# DCDC-LMR16030.net
KiCad netlist of a schematic drawn in Altium Designer
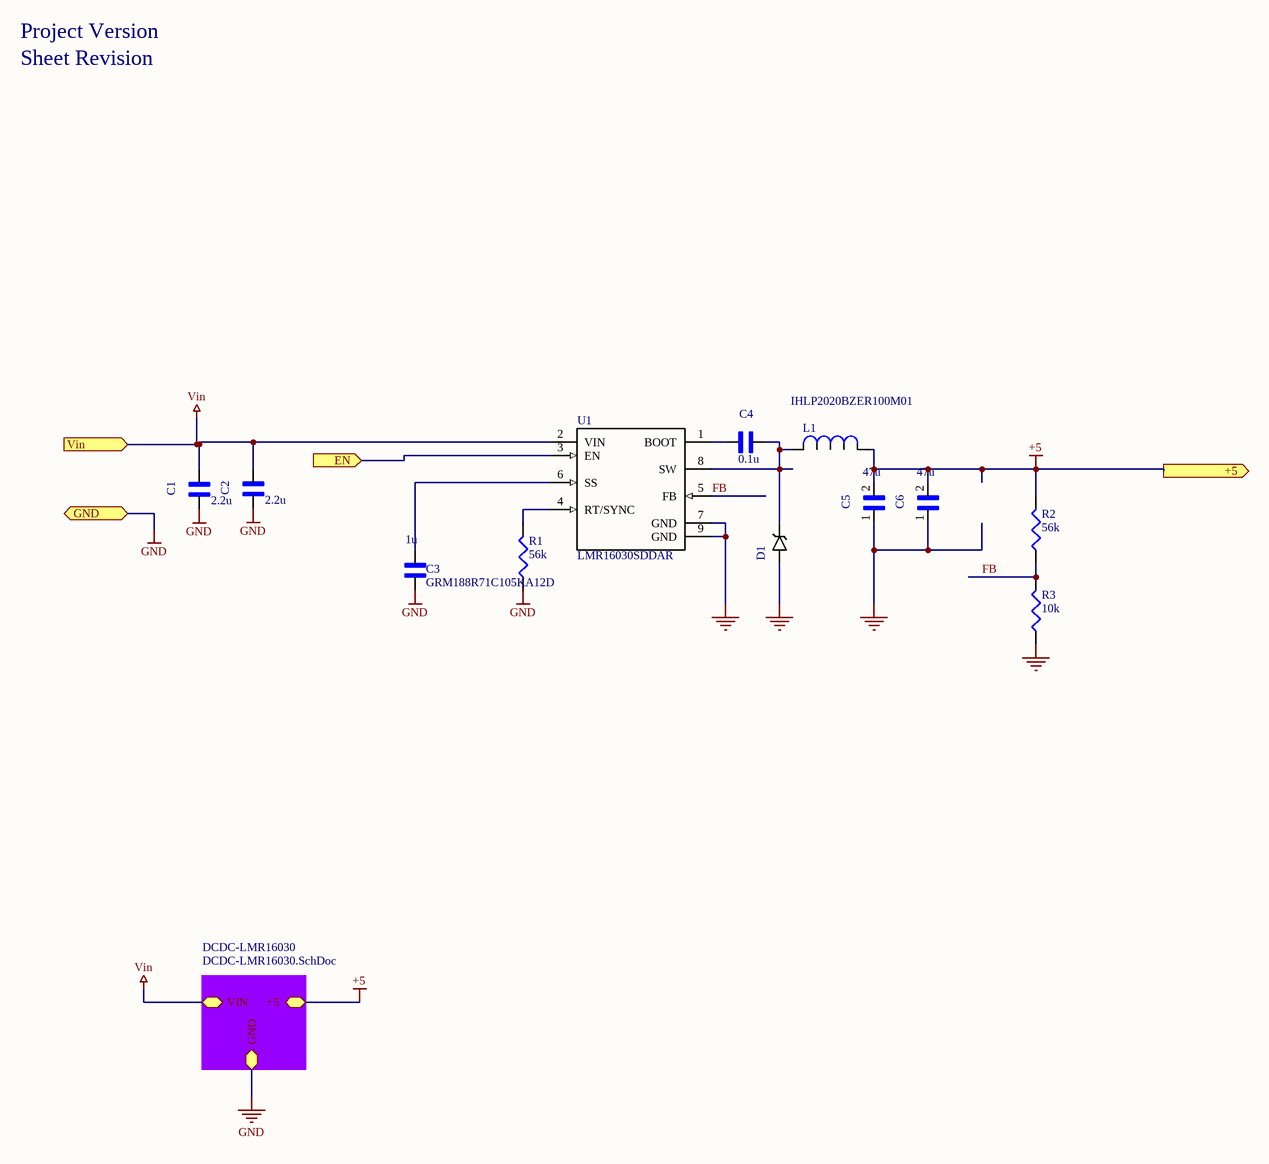
[diagram p0: DCDC-LMR16030.SchDoc]

(export (version "E")
  (design (tool "Eeschema 10.0.6"))
  (components
    (comp (ref "C1")
      (value "2.2u")
      (footprint "*CAP3216X125N")
      (description "1206 2.2 uF 50 V В±10% Tolerance X7R SMT Multilayer Ceramic Capacitor")
      (fields (field (name "MF") "Murata Electronics") (field (name "MP") "GRM31CR71H225KA88L"))
      (libsource (lib "lib") (part "GRM31CR71H225KA88L"))
    )
    (comp (ref "C2")
      (value "2.2u")
      (footprint "*CAP3216X125N")
      (description "1206 2.2 uF 50 V В±10% Tolerance X7R SMT Multilayer Ceramic Capacitor")
      (fields (field (name "MF") "Murata Electronics") (field (name "MP") "GRM31CR71H225KA88L"))
      (libsource (lib "lib") (part "GRM31CR71H225KA88L"))
    )
    (comp (ref "C3")
      (value "GRM188R71C105KA12D")
      (footprint "CAPC1608X90N")
      (description "SMD Capacitor X7R(EIA) with Capacitance: 1.0uF Tol. 10%. Rated Voltage: 16Vdc")
      (fields (field (name "MF") "Murata Electronics") (field (name "ALTIUM_VALUE") "1u"))
      (libsource (lib "lib") (part "GRM188R71C105KA12D"))
    )
    (comp (ref "C4")
      (value "0.1u")
      (footprint "*CAPC1608X90")
      (description "Cap Thin Film 0.1uf 50v 0603")
      (fields (field (name "MF") "AVX") (field (name "MP") "GX035C104MAT2-500 or CL10B104JB8NNNC"))
      (libsource (lib "lib") (part "GX035C104MAT2-500"))
    )
    (comp (ref "C5")
      (value "47u")
      (footprint "*CAPC3216X125N")
      (description "Multilayer Ceramic Capacitor, GRM Series, 47 - F, - 10%, X5R, 10 V, 1206 [3216 Metric]")
      (fields (field (name "MF") "Murata Electronics") (field (name "MP") "GRM31CR61A476KE15L"))
      (libsource (lib "lib") (part "GRM31CR61A476KE15L"))
    )
    (comp (ref "C6")
      (value "47u")
      (footprint "*CAPC3216X125N")
      (description "Multilayer Ceramic Capacitor, GRM Series, 47 - F, - 10%, X5R, 10 V, 1206 [3216 Metric]")
      (fields (field (name "MF") "Murata Electronics") (field (name "MP") "GRM31CR61A476KE15L"))
      (libsource (lib "lib") (part "GRM31CR61A476KE15L"))
    )
    (comp (ref "D1")
      (value "SK56")
      (footprint "*SMB_P6SMB62AT3G(Primary)")
      (description "Диод Шоттки 5А 60В [SMB / DO-214AA]")
      (fields (field (name "MF") "Littelfuse Inc."))
      (libsource (lib "lib") (part "SK56"))
    )
    (comp (ref "L1")
      (value "IHLP2020BZER100M01")
      (footprint "IHLP")
      (description "10ÂµH Shielded Molded Inductor 2.3A 199mOhm Max Nonstandard")
      (fields (field (name "MF") "Vishay Dale"))
      (libsource (lib "lib") (part "IHLP2020BZER100M01"))
    )
    (comp (ref "R1")
      (value "56k")
      (footprint "J1-0603")
      (description "Resistor")
      (fields (field (name "MP") "RC0603FR-0756KL") (field (name "Comment") "Res3"))
      (libsource (lib "Miscellaneous Devices") (part "Res3"))
    )
    (comp (ref "R2")
      (value "56k")
      (footprint "J1-0603")
      (description "Resistor")
      (fields (field (name "MP") "RC0603FR-0756KL") (field (name "Comment") "Res3"))
      (libsource (lib "Miscellaneous Devices") (part "Res3"))
    )
    (comp (ref "R3")
      (value "10k")
      (footprint "J1-0603")
      (description "10 kOhms 1 0.1 W 1 10 W Chip Resistor 0603 1608 Metric Thick Film")
      (fields (field (name "MF") "Yageo or NXP") (field (name "MP") "10K 1% 0603"))
      (libsource (lib "CAN_NODE_MINI") (part "RC0603FR-0710KL"))
    )
    (comp (ref "U1")
      (value "LMR16030SDDAR")
      (footprint "*SOIC127P600X170-9N - duplicate")
      (fields (field (name "MF") "Texas Instruments"))
      (libsource (lib "lib") (part "LMR16030SDDAR"))
    )
  )
  (nets
    (net (code "1") (name "+5") (class "Default")
      (node (ref "C5") (pin "2") (pinfunction "2_2") (pintype "passive"))
      (node (ref "C6") (pin "2") (pinfunction "2_2") (pintype "passive"))
      (node (ref "L1") (pin "1") (pinfunction "1_1") (pintype "passive"))
      (node (ref "R2") (pin "2") (pinfunction "2_2") (pintype "passive"))
    )
    (net (code "2") (name "/EN") (class "Default")
      (node (ref "U1") (pin "3") (pinfunction "EN_3") (pintype "input"))
    )
    (net (code "3") (name "/FB") (class "Default")
      (node (ref "R2") (pin "1") (pinfunction "1_1") (pintype "passive"))
      (node (ref "R3") (pin "2") (pinfunction "2_2") (pintype "passive"))
      (node (ref "U1") (pin "5") (pinfunction "FB_5") (pintype "input"))
    )
    (net (code "4") (name "GND") (class "Default")
      (node (ref "C1") (pin "2") (pinfunction "2_2") (pintype "passive"))
      (node (ref "C2") (pin "2") (pinfunction "2_2") (pintype "passive"))
      (node (ref "C3") (pin "1") (pinfunction "1_1") (pintype "passive"))
      (node (ref "C5") (pin "1") (pinfunction "1_1") (pintype "passive"))
      (node (ref "C6") (pin "1") (pinfunction "1_1") (pintype "passive"))
      (node (ref "D1") (pin "A") (pinfunction "A_A") (pintype "power_in"))
      (node (ref "R1") (pin "1") (pinfunction "1_1") (pintype "passive"))
      (node (ref "R3") (pin "1") (pinfunction "1_1") (pintype "passive"))
      (node (ref "U1") (pin "7") (pinfunction "GND_7") (pintype "power_in"))
      (node (ref "U1") (pin "9") (pinfunction "GND_9") (pintype "power_in"))
    )
    (net (code "5") (name "Net-(U1-BOOT)") (class "Default")
      (node (ref "C4") (pin "2") (pinfunction "2_2") (pintype "passive"))
      (node (ref "U1") (pin "1") (pinfunction "BOOT_1") (pintype "power_in"))
    )
    (net (code "6") (name "Net-(U1-RT{slash}SYNC)") (class "Default")
      (node (ref "R1") (pin "2") (pinfunction "2_2") (pintype "passive"))
      (node (ref "U1") (pin "4") (pinfunction "RT/SYNC_4") (pintype "input"))
    )
    (net (code "7") (name "Net-(U1-SS)") (class "Default")
      (node (ref "C3") (pin "2") (pinfunction "2_2") (pintype "passive"))
      (node (ref "U1") (pin "6") (pinfunction "SS_6") (pintype "input"))
    )
    (net (code "8") (name "Net-(U1-SW)") (class "Default")
      (node (ref "C4") (pin "1") (pinfunction "1_1") (pintype "passive"))
      (node (ref "D1") (pin "C") (pinfunction "C_C") (pintype "power_in"))
      (node (ref "L1") (pin "2") (pinfunction "2_2") (pintype "passive"))
      (node (ref "U1") (pin "8") (pinfunction "SW_8") (pintype "power_in"))
    )
    (net (code "9") (name "Vin") (class "Default")
      (node (ref "C1") (pin "1") (pinfunction "1_1") (pintype "passive"))
      (node (ref "C2") (pin "1") (pinfunction "1_1") (pintype "passive"))
      (node (ref "U1") (pin "2") (pinfunction "VIN_2") (pintype "power_in"))
    )
  )
)
